# CEM-8bit-PCA9557.net
KiCad netlist of a schematic drawn in EAGLE
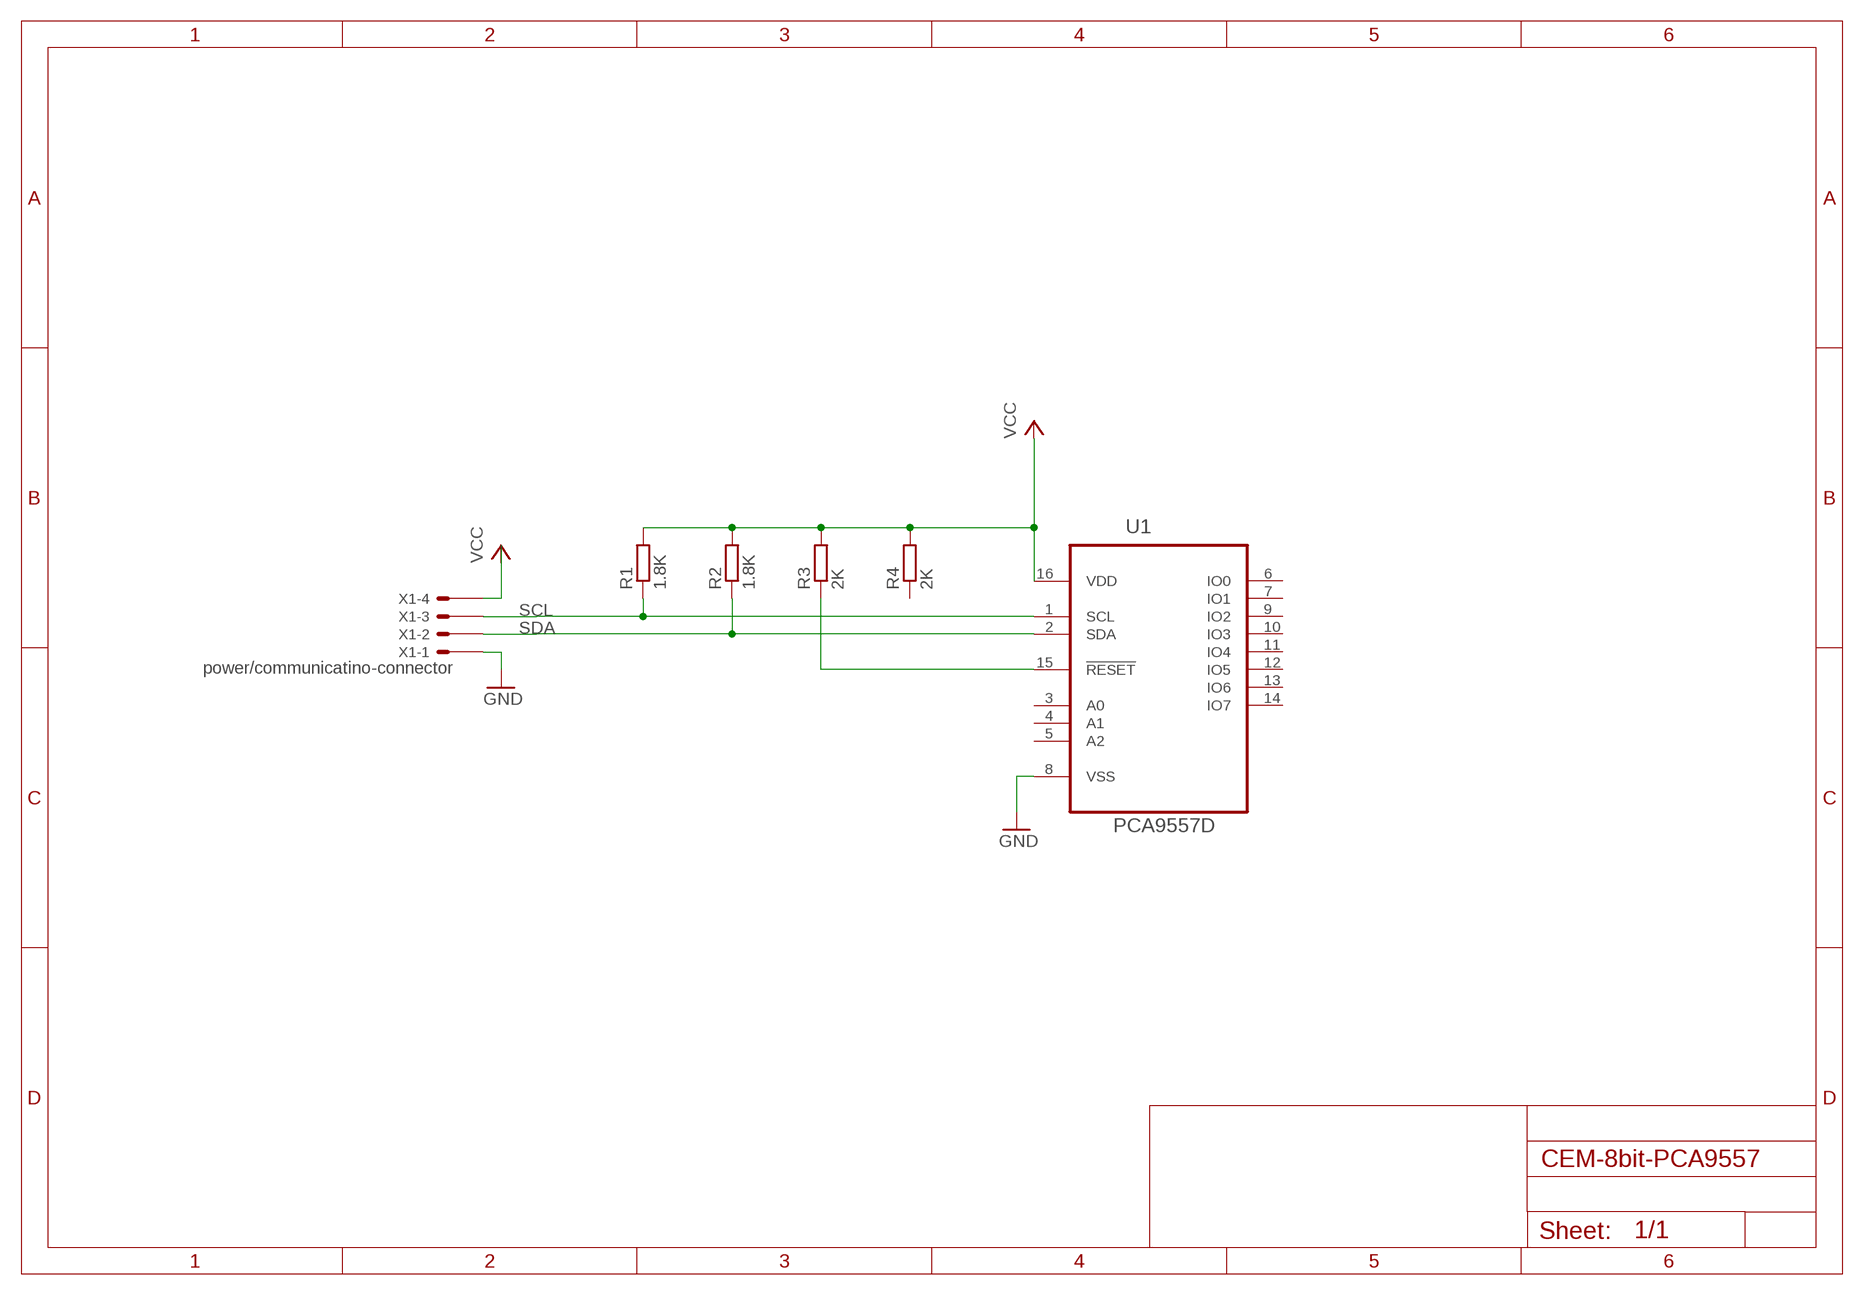
[diagram p0: schematic, sheet 1]

(export (version "E")
  (design (tool "Eeschema 10.0.6"))
  (components
    (comp (ref "R1")
      (value "1.8K")
      (footprint "eagle-import:MINI_MELF-0204R")
      (libsource (lib "eagle-import") (part "R-EU_MELF0204R"))
    )
    (comp (ref "R2")
      (value "1.8K")
      (footprint "eagle-import:MINI_MELF-0204R")
      (libsource (lib "eagle-import") (part "R-EU_MELF0204R"))
    )
    (comp (ref "R3")
      (value "2K")
      (footprint "eagle-import:MINI_MELF-0204R")
      (libsource (lib "eagle-import") (part "R-EU_MELF0204R"))
    )
    (comp (ref "R4")
      (value "2K")
      (footprint "eagle-import:MINI_MELF-0204R")
      (libsource (lib "eagle-import") (part "R-EU_MELF0204R"))
    )
    (comp (ref "U1")
      (value "PCA9557D")
      (footprint "eagle-import:SOIC127P600X175-16N")
      (libsource (lib "eagle-import") (part "PCA9557D"))
    )
    (comp (ref "X1")
      (value "power/communicatino-connector")
      (footprint "eagle-import:43160-XX04")
      (fields (field (name "MF") "WALDOM/MOLEX") (field (name "MPN") "43160-1104"))
      (libsource (lib "eagle-import") (part "43160-0411"))
    )
  )
  (nets
    (net (code "1") (name "/SCL") (class "Default")
      (node (ref "R1") (pin "1") (pinfunction "1_1") (pintype "passive"))
      (node (ref "U1") (pin "1") (pinfunction "SCL_1") (pintype "input"))
      (node (ref "X1") (pin "3@1") (pinfunction "S_3@1") (pintype "passive"))
    )
    (net (code "2") (name "/SDA") (class "Default")
      (node (ref "R2") (pin "1") (pinfunction "1_1") (pintype "passive"))
      (node (ref "U1") (pin "2") (pinfunction "SDA_2") (pintype "bidirectional"))
      (node (ref "X1") (pin "2@1") (pinfunction "S_2@1") (pintype "passive"))
    )
    (net (code "3") (name "GND") (class "Default")
      (node (ref "U1") (pin "8") (pinfunction "VSS_8") (pintype "passive"))
      (node (ref "X1") (pin "1@1") (pinfunction "S_1@1") (pintype "passive"))
    )
    (net (code "4") (name "Net-(U1-~{RESET})") (class "Default")
      (node (ref "R3") (pin "1") (pinfunction "1_1") (pintype "passive"))
      (node (ref "U1") (pin "15") (pinfunction "~{RESET}_15") (pintype "input"))
    )
    (net (code "5") (name "VCC") (class "Default")
      (node (ref "R1") (pin "2") (pinfunction "2_2") (pintype "passive"))
      (node (ref "R2") (pin "2") (pinfunction "2_2") (pintype "passive"))
      (node (ref "R3") (pin "2") (pinfunction "2_2") (pintype "passive"))
      (node (ref "R4") (pin "2") (pinfunction "2_2") (pintype "passive"))
      (node (ref "U1") (pin "16") (pinfunction "VDD_16") (pintype "power_in"))
      (node (ref "X1") (pin "4@1") (pinfunction "S_4@1") (pintype "passive"))
    )
    (net (code "6") (name "unconnected-(R4-Pad1)") (class "Default")
      (node (ref "R4") (pin "1") (pinfunction "1_1") (pintype "passive"))
    )
    (net (code "7") (name "unconnected-(U1-A0-Pad3)") (class "Default")
      (node (ref "U1") (pin "3") (pinfunction "A0_3") (pintype "input"))
    )
    (net (code "8") (name "unconnected-(U1-A1-Pad4)") (class "Default")
      (node (ref "U1") (pin "4") (pinfunction "A1_4") (pintype "input"))
    )
    (net (code "9") (name "unconnected-(U1-A2-Pad5)") (class "Default")
      (node (ref "U1") (pin "5") (pinfunction "A2_5") (pintype "input"))
    )
    (net (code "10") (name "unconnected-(U1-IO0-Pad6)") (class "Default")
      (node (ref "U1") (pin "6") (pinfunction "IO0_6") (pintype "bidirectional"))
    )
    (net (code "11") (name "unconnected-(U1-IO1-Pad7)") (class "Default")
      (node (ref "U1") (pin "7") (pinfunction "IO1_7") (pintype "bidirectional"))
    )
    (net (code "12") (name "unconnected-(U1-IO2-Pad9)") (class "Default")
      (node (ref "U1") (pin "9") (pinfunction "IO2_9") (pintype "bidirectional"))
    )
    (net (code "13") (name "unconnected-(U1-IO3-Pad10)") (class "Default")
      (node (ref "U1") (pin "10") (pinfunction "IO3_10") (pintype "bidirectional"))
    )
    (net (code "14") (name "unconnected-(U1-IO4-Pad11)") (class "Default")
      (node (ref "U1") (pin "11") (pinfunction "IO4_11") (pintype "bidirectional"))
    )
    (net (code "15") (name "unconnected-(U1-IO5-Pad12)") (class "Default")
      (node (ref "U1") (pin "12") (pinfunction "IO5_12") (pintype "bidirectional"))
    )
    (net (code "16") (name "unconnected-(U1-IO6-Pad13)") (class "Default")
      (node (ref "U1") (pin "13") (pinfunction "IO6_13") (pintype "bidirectional"))
    )
    (net (code "17") (name "unconnected-(U1-IO7-Pad14)") (class "Default")
      (node (ref "U1") (pin "14") (pinfunction "IO7_14") (pintype "bidirectional"))
    )
    (net (code "18") (name "unconnected-(X1A-S-Pad1@2)") (class "Default")
      (node (ref "X1") (pin "1@2") (pinfunction "S_1@2") (pintype "passive"))
    )
    (net (code "19") (name "unconnected-(X1B-S-Pad2@2)") (class "Default")
      (node (ref "X1") (pin "2@2") (pinfunction "S_2@2") (pintype "passive"))
    )
    (net (code "20") (name "unconnected-(X1C-S-Pad3@2)") (class "Default")
      (node (ref "X1") (pin "3@2") (pinfunction "S_3@2") (pintype "passive"))
    )
    (net (code "21") (name "unconnected-(X1D-S-Pad4@2)") (class "Default")
      (node (ref "X1") (pin "4@2") (pinfunction "S_4@2") (pintype "passive"))
    )
  )
)
